# W607B.net
KiCad netlist of a schematic drawn in EAGLE
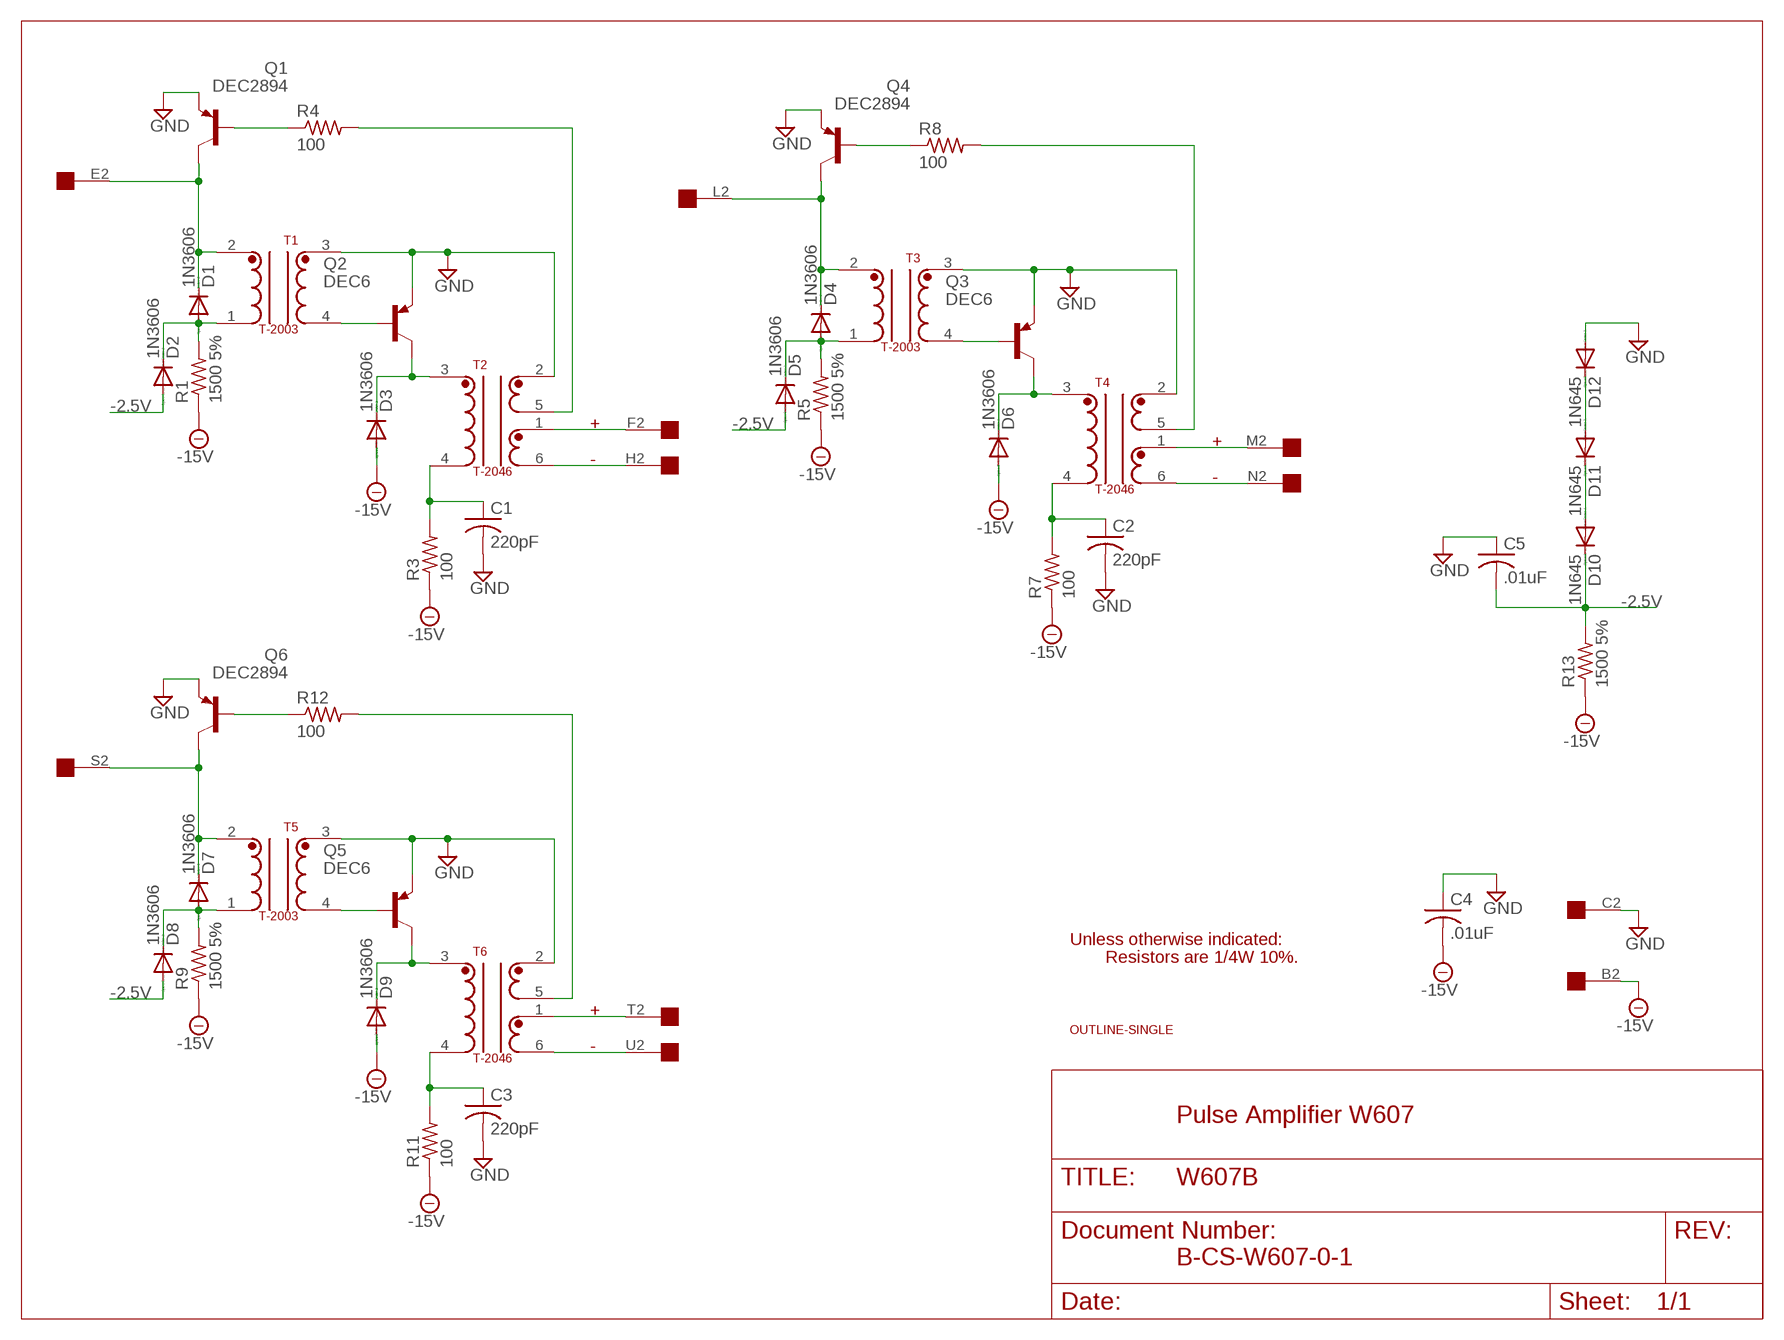
[diagram p0: schematic, sheet 1]

(export (version "E")
  (design (tool "Eeschema 10.0.6"))
  (components
    (comp (ref "C1")
      (value "220pF")
      (footprint "eagle-import:C050-025X075")
      (libsource (lib "eagle-import") (part "C-US050-025X075"))
    )
    (comp (ref "C2")
      (value "220pF")
      (footprint "eagle-import:C050-025X075")
      (libsource (lib "eagle-import") (part "C-US050-025X075"))
    )
    (comp (ref "C3")
      (value "220pF")
      (footprint "eagle-import:C050-025X075")
      (libsource (lib "eagle-import") (part "C-US050-025X075"))
    )
    (comp (ref "C4")
      (value ".01uF")
      (footprint "eagle-import:C050-025X075")
      (libsource (lib "eagle-import") (part "C-US050-025X075"))
    )
    (comp (ref "C5")
      (value ".01uF")
      (footprint "eagle-import:C050-025X075")
      (libsource (lib "eagle-import") (part "C-US050-025X075"))
    )
    (comp (ref "D1")
      (value "1N3606")
      (footprint "eagle-import:DO35-10")
      (libsource (lib "eagle-import") (part "1N4148DO35-10"))
    )
    (comp (ref "D2")
      (value "1N3606")
      (footprint "eagle-import:DO35-10")
      (libsource (lib "eagle-import") (part "1N4148DO35-10"))
    )
    (comp (ref "D3")
      (value "1N3606")
      (footprint "eagle-import:DO35-10")
      (libsource (lib "eagle-import") (part "1N4148DO35-10"))
    )
    (comp (ref "D4")
      (value "1N3606")
      (footprint "eagle-import:DO35-10")
      (libsource (lib "eagle-import") (part "1N4148DO35-10"))
    )
    (comp (ref "D5")
      (value "1N3606")
      (footprint "eagle-import:DO35-10")
      (libsource (lib "eagle-import") (part "1N4148DO35-10"))
    )
    (comp (ref "D6")
      (value "1N3606")
      (footprint "eagle-import:DO35-10")
      (libsource (lib "eagle-import") (part "1N4148DO35-10"))
    )
    (comp (ref "D7")
      (value "1N3606")
      (footprint "eagle-import:DO35-10")
      (libsource (lib "eagle-import") (part "1N4148DO35-10"))
    )
    (comp (ref "D8")
      (value "1N3606")
      (footprint "eagle-import:DO35-10")
      (libsource (lib "eagle-import") (part "1N4148DO35-10"))
    )
    (comp (ref "D9")
      (value "1N3606")
      (footprint "eagle-import:DO35-10")
      (libsource (lib "eagle-import") (part "1N4148DO35-10"))
    )
    (comp (ref "D10")
      (value "1N645")
      (footprint "eagle-import:DO35-10")
      (libsource (lib "eagle-import") (part "1N4148DO35-10"))
    )
    (comp (ref "D11")
      (value "1N645")
      (footprint "eagle-import:DO35-10")
      (libsource (lib "eagle-import") (part "1N4148DO35-10"))
    )
    (comp (ref "D12")
      (value "1N645")
      (footprint "eagle-import:DO35-10")
      (libsource (lib "eagle-import") (part "1N4148DO35-10"))
    )
    (comp (ref "Q1")
      (value "DEC2894")
      (footprint "eagle-import:TO39")
      (libsource (lib "eagle-import") (part "2N2904"))
    )
    (comp (ref "Q2")
      (value "DEC6")
      (footprint "eagle-import:TO39")
      (libsource (lib "eagle-import") (part "2N2904"))
    )
    (comp (ref "Q3")
      (value "DEC6")
      (footprint "eagle-import:TO39")
      (libsource (lib "eagle-import") (part "2N2904"))
    )
    (comp (ref "Q4")
      (value "DEC2894")
      (footprint "eagle-import:TO39")
      (libsource (lib "eagle-import") (part "2N2904"))
    )
    (comp (ref "Q5")
      (value "DEC6")
      (footprint "eagle-import:TO39")
      (libsource (lib "eagle-import") (part "2N2904"))
    )
    (comp (ref "Q6")
      (value "DEC2894")
      (footprint "eagle-import:TO39")
      (libsource (lib "eagle-import") (part "2N2904"))
    )
    (comp (ref "R1")
      (value "1500 5%")
      (footprint "eagle-import:0207_10")
      (libsource (lib "eagle-import") (part "R-US_0207/10"))
    )
    (comp (ref "R3")
      (value "100")
      (footprint "eagle-import:0207_10")
      (libsource (lib "eagle-import") (part "R-US_0207/10"))
    )
    (comp (ref "R4")
      (value "100")
      (footprint "eagle-import:0207_10")
      (libsource (lib "eagle-import") (part "R-US_0207/10"))
    )
    (comp (ref "R5")
      (value "1500 5%")
      (footprint "eagle-import:0207_10")
      (libsource (lib "eagle-import") (part "R-US_0207/10"))
    )
    (comp (ref "R7")
      (value "100")
      (footprint "eagle-import:0207_10")
      (libsource (lib "eagle-import") (part "R-US_0207/10"))
    )
    (comp (ref "R8")
      (value "100")
      (footprint "eagle-import:0207_10")
      (libsource (lib "eagle-import") (part "R-US_0207/10"))
    )
    (comp (ref "R9")
      (value "1500 5%")
      (footprint "eagle-import:0207_10")
      (libsource (lib "eagle-import") (part "R-US_0207/10"))
    )
    (comp (ref "R11")
      (value "100")
      (footprint "eagle-import:0207_10")
      (libsource (lib "eagle-import") (part "R-US_0207/10"))
    )
    (comp (ref "R12")
      (value "100")
      (footprint "eagle-import:0207_10")
      (libsource (lib "eagle-import") (part "R-US_0207/10"))
    )
    (comp (ref "R13")
      (value "1500 5%")
      (footprint "eagle-import:0207_10")
      (libsource (lib "eagle-import") (part "R-US_0207/10"))
    )
    (comp (ref "T1")
      (value "T-2003")
      (footprint "eagle-import:TRANSFORMER2")
      (libsource (lib "eagle-import") (part "T-2010"))
    )
    (comp (ref "T2")
      (value "T-2046")
      (footprint "eagle-import:TRANSFORMER6")
      (libsource (lib "eagle-import") (part "T-2046"))
    )
    (comp (ref "T3")
      (value "T-2003")
      (footprint "eagle-import:TRANSFORMER2")
      (libsource (lib "eagle-import") (part "T-2010"))
    )
    (comp (ref "T4")
      (value "T-2046")
      (footprint "eagle-import:TRANSFORMER6")
      (libsource (lib "eagle-import") (part "T-2046"))
    )
    (comp (ref "T5")
      (value "T-2003")
      (footprint "eagle-import:TRANSFORMER2")
      (libsource (lib "eagle-import") (part "T-2010"))
    )
    (comp (ref "T6")
      (value "T-2046")
      (footprint "eagle-import:TRANSFORMER6")
      (libsource (lib "eagle-import") (part "T-2046"))
    )
    (comp (ref "U$1")
      (value "OUTLINE-SINGLE")
      (footprint "eagle-import:SINGLE")
      (libsource (lib "eagle-import") (part "OUTLINE-SINGLE"))
    )
    (comp (ref "U$2")
      (value "EDGE-1")
      (footprint "eagle-import:EDGE-CON1")
      (libsource (lib "eagle-import") (part "EDGE-1"))
    )
  )
  (nets
    (net (code "1") (name "-15V") (class "Default")
      (node (ref "C4") (pin "2") (pinfunction "2_2") (pintype "passive"))
      (node (ref "D3") (pin "A") (pinfunction "A_A") (pintype "passive"))
      (node (ref "D6") (pin "A") (pinfunction "A_A") (pintype "passive"))
      (node (ref "D9") (pin "A") (pinfunction "A_A") (pintype "passive"))
      (node (ref "R1") (pin "1") (pinfunction "1_1") (pintype "passive"))
      (node (ref "R11") (pin "1") (pinfunction "1_1") (pintype "passive"))
      (node (ref "R13") (pin "1") (pinfunction "1_1") (pintype "passive"))
      (node (ref "R3") (pin "1") (pinfunction "1_1") (pintype "passive"))
      (node (ref "R5") (pin "1") (pinfunction "1_1") (pintype "passive"))
      (node (ref "R7") (pin "1") (pinfunction "1_1") (pintype "passive"))
      (node (ref "R9") (pin "1") (pinfunction "1_1") (pintype "passive"))
      (node (ref "U$2") (pin "B2") (pinfunction "1_B2") (pintype "bidirectional"))
    )
    (net (code "2") (name "/-2.5V") (class "Default")
      (node (ref "C5") (pin "2") (pinfunction "2_2") (pintype "passive"))
      (node (ref "D10") (pin "C") (pinfunction "C_C") (pintype "passive"))
      (node (ref "D2") (pin "A") (pinfunction "A_A") (pintype "passive"))
      (node (ref "D5") (pin "A") (pinfunction "A_A") (pintype "passive"))
      (node (ref "D8") (pin "A") (pinfunction "A_A") (pintype "passive"))
      (node (ref "R13") (pin "2") (pinfunction "2_2") (pintype "passive"))
    )
    (net (code "3") (name "GND") (class "Default")
      (node (ref "C1") (pin "2") (pinfunction "2_2") (pintype "passive"))
      (node (ref "C2") (pin "2") (pinfunction "2_2") (pintype "passive"))
      (node (ref "C3") (pin "2") (pinfunction "2_2") (pintype "passive"))
      (node (ref "C4") (pin "1") (pinfunction "1_1") (pintype "passive"))
      (node (ref "C5") (pin "1") (pinfunction "1_1") (pintype "passive"))
      (node (ref "D12") (pin "A") (pinfunction "A_A") (pintype "passive"))
      (node (ref "Q1") (pin "1") (pinfunction "E_1") (pintype "passive"))
      (node (ref "Q2") (pin "1") (pinfunction "E_1") (pintype "passive"))
      (node (ref "Q3") (pin "1") (pinfunction "E_1") (pintype "passive"))
      (node (ref "Q4") (pin "1") (pinfunction "E_1") (pintype "passive"))
      (node (ref "Q5") (pin "1") (pinfunction "E_1") (pintype "passive"))
      (node (ref "Q6") (pin "1") (pinfunction "E_1") (pintype "passive"))
      (node (ref "T1") (pin "3") (pinfunction "P$2_3") (pintype "passive"))
      (node (ref "T2") (pin "2") (pinfunction "2_2") (pintype "passive"))
      (node (ref "T3") (pin "3") (pinfunction "P$2_3") (pintype "passive"))
      (node (ref "T4") (pin "2") (pinfunction "2_2") (pintype "passive"))
      (node (ref "T5") (pin "3") (pinfunction "P$2_3") (pintype "passive"))
      (node (ref "T6") (pin "2") (pinfunction "2_2") (pintype "passive"))
      (node (ref "U$2") (pin "C2") (pinfunction "1_C2") (pintype "bidirectional"))
    )
    (net (code "4") (name "Net-(C1-Pad1)") (class "Default")
      (node (ref "C1") (pin "1") (pinfunction "1_1") (pintype "passive"))
      (node (ref "R3") (pin "2") (pinfunction "2_2") (pintype "passive"))
      (node (ref "T2") (pin "4") (pinfunction "4_4") (pintype "passive"))
    )
    (net (code "5") (name "Net-(C2-Pad1)") (class "Default")
      (node (ref "C2") (pin "1") (pinfunction "1_1") (pintype "passive"))
      (node (ref "R7") (pin "2") (pinfunction "2_2") (pintype "passive"))
      (node (ref "T4") (pin "4") (pinfunction "4_4") (pintype "passive"))
    )
    (net (code "6") (name "Net-(C3-Pad1)") (class "Default")
      (node (ref "C3") (pin "1") (pinfunction "1_1") (pintype "passive"))
      (node (ref "R11") (pin "2") (pinfunction "2_2") (pintype "passive"))
      (node (ref "T6") (pin "4") (pinfunction "4_4") (pintype "passive"))
    )
    (net (code "7") (name "Net-(D10-PadA)") (class "Default")
      (node (ref "D10") (pin "A") (pinfunction "A_A") (pintype "passive"))
      (node (ref "D11") (pin "C") (pinfunction "C_C") (pintype "passive"))
    )
    (net (code "8") (name "Net-(D11-PadA)") (class "Default")
      (node (ref "D11") (pin "A") (pinfunction "A_A") (pintype "passive"))
      (node (ref "D12") (pin "C") (pinfunction "C_C") (pintype "passive"))
    )
    (net (code "9") (name "Net-(Q1-B)") (class "Default")
      (node (ref "Q1") (pin "2") (pinfunction "B_2") (pintype "passive"))
      (node (ref "R4") (pin "1") (pinfunction "1_1") (pintype "passive"))
    )
    (net (code "10") (name "Net-(Q1-C)") (class "Default")
      (node (ref "D1") (pin "C") (pinfunction "C_C") (pintype "passive"))
      (node (ref "Q1") (pin "3") (pinfunction "C_3") (pintype "passive"))
      (node (ref "T1") (pin "2") (pinfunction "P$4_2") (pintype "passive"))
      (node (ref "U$2") (pin "E2") (pinfunction "1_E2") (pintype "bidirectional"))
    )
    (net (code "11") (name "Net-(Q2-B)") (class "Default")
      (node (ref "Q2") (pin "2") (pinfunction "B_2") (pintype "passive"))
      (node (ref "T1") (pin "4") (pinfunction "P$7_4") (pintype "passive"))
    )
    (net (code "12") (name "Net-(Q2-C)") (class "Default")
      (node (ref "D3") (pin "C") (pinfunction "C_C") (pintype "passive"))
      (node (ref "Q2") (pin "3") (pinfunction "C_3") (pintype "passive"))
      (node (ref "T2") (pin "3") (pinfunction "3_3") (pintype "passive"))
    )
    (net (code "13") (name "Net-(Q3-B)") (class "Default")
      (node (ref "Q3") (pin "2") (pinfunction "B_2") (pintype "passive"))
      (node (ref "T3") (pin "4") (pinfunction "P$7_4") (pintype "passive"))
    )
    (net (code "14") (name "Net-(Q3-C)") (class "Default")
      (node (ref "D6") (pin "C") (pinfunction "C_C") (pintype "passive"))
      (node (ref "Q3") (pin "3") (pinfunction "C_3") (pintype "passive"))
      (node (ref "T4") (pin "3") (pinfunction "3_3") (pintype "passive"))
    )
    (net (code "15") (name "Net-(Q4-B)") (class "Default")
      (node (ref "Q4") (pin "2") (pinfunction "B_2") (pintype "passive"))
      (node (ref "R8") (pin "1") (pinfunction "1_1") (pintype "passive"))
    )
    (net (code "16") (name "Net-(Q4-C)") (class "Default")
      (node (ref "D4") (pin "C") (pinfunction "C_C") (pintype "passive"))
      (node (ref "Q4") (pin "3") (pinfunction "C_3") (pintype "passive"))
      (node (ref "T3") (pin "2") (pinfunction "P$4_2") (pintype "passive"))
      (node (ref "U$2") (pin "L2") (pinfunction "1_L2") (pintype "bidirectional"))
    )
    (net (code "17") (name "Net-(Q5-B)") (class "Default")
      (node (ref "Q5") (pin "2") (pinfunction "B_2") (pintype "passive"))
      (node (ref "T5") (pin "4") (pinfunction "P$7_4") (pintype "passive"))
    )
    (net (code "18") (name "Net-(Q5-C)") (class "Default")
      (node (ref "D9") (pin "C") (pinfunction "C_C") (pintype "passive"))
      (node (ref "Q5") (pin "3") (pinfunction "C_3") (pintype "passive"))
      (node (ref "T6") (pin "3") (pinfunction "3_3") (pintype "passive"))
    )
    (net (code "19") (name "Net-(Q6-B)") (class "Default")
      (node (ref "Q6") (pin "2") (pinfunction "B_2") (pintype "passive"))
      (node (ref "R12") (pin "1") (pinfunction "1_1") (pintype "passive"))
    )
    (net (code "20") (name "Net-(Q6-C)") (class "Default")
      (node (ref "D7") (pin "C") (pinfunction "C_C") (pintype "passive"))
      (node (ref "Q6") (pin "3") (pinfunction "C_3") (pintype "passive"))
      (node (ref "T5") (pin "2") (pinfunction "P$4_2") (pintype "passive"))
      (node (ref "U$2") (pin "S2") (pinfunction "1_S2") (pintype "bidirectional"))
    )
    (net (code "21") (name "Net-(R4-Pad2)") (class "Default")
      (node (ref "R4") (pin "2") (pinfunction "2_2") (pintype "passive"))
      (node (ref "T2") (pin "5") (pinfunction "5_5") (pintype "passive"))
    )
    (net (code "22") (name "Net-(R8-Pad2)") (class "Default")
      (node (ref "R8") (pin "2") (pinfunction "2_2") (pintype "passive"))
      (node (ref "T4") (pin "5") (pinfunction "5_5") (pintype "passive"))
    )
    (net (code "23") (name "Net-(R12-Pad2)") (class "Default")
      (node (ref "R12") (pin "2") (pinfunction "2_2") (pintype "passive"))
      (node (ref "T6") (pin "5") (pinfunction "5_5") (pintype "passive"))
    )
    (net (code "24") (name "Net-(T1-P$5)") (class "Default")
      (node (ref "D1") (pin "A") (pinfunction "A_A") (pintype "passive"))
      (node (ref "D2") (pin "C") (pinfunction "C_C") (pintype "passive"))
      (node (ref "R1") (pin "2") (pinfunction "2_2") (pintype "passive"))
      (node (ref "T1") (pin "1") (pinfunction "P$5_1") (pintype "passive"))
    )
    (net (code "25") (name "Net-(T3-P$5)") (class "Default")
      (node (ref "D4") (pin "A") (pinfunction "A_A") (pintype "passive"))
      (node (ref "D5") (pin "C") (pinfunction "C_C") (pintype "passive"))
      (node (ref "R5") (pin "2") (pinfunction "2_2") (pintype "passive"))
      (node (ref "T3") (pin "1") (pinfunction "P$5_1") (pintype "passive"))
    )
    (net (code "26") (name "Net-(T5-P$5)") (class "Default")
      (node (ref "D7") (pin "A") (pinfunction "A_A") (pintype "passive"))
      (node (ref "D8") (pin "C") (pinfunction "C_C") (pintype "passive"))
      (node (ref "R9") (pin "2") (pinfunction "2_2") (pintype "passive"))
      (node (ref "T5") (pin "1") (pinfunction "P$5_1") (pintype "passive"))
    )
    (net (code "27") (name "Net-(U$2F-1)") (class "Default")
      (node (ref "T2") (pin "1") (pinfunction "1_1") (pintype "passive"))
      (node (ref "U$2") (pin "F2") (pinfunction "1_F2") (pintype "bidirectional"))
    )
    (net (code "28") (name "Net-(U$2G-1)") (class "Default")
      (node (ref "T2") (pin "6") (pinfunction "6_6") (pintype "passive"))
      (node (ref "U$2") (pin "H2") (pinfunction "1_H2") (pintype "bidirectional"))
    )
    (net (code "29") (name "Net-(U$2K-1)") (class "Default")
      (node (ref "T4") (pin "1") (pinfunction "1_1") (pintype "passive"))
      (node (ref "U$2") (pin "M2") (pinfunction "1_M2") (pintype "bidirectional"))
    )
    (net (code "30") (name "Net-(U$2L-1)") (class "Default")
      (node (ref "T4") (pin "6") (pinfunction "6_6") (pintype "passive"))
      (node (ref "U$2") (pin "N2") (pinfunction "1_N2") (pintype "bidirectional"))
    )
    (net (code "31") (name "Net-(U$2P-1)") (class "Default")
      (node (ref "T6") (pin "1") (pinfunction "1_1") (pintype "passive"))
      (node (ref "U$2") (pin "T2") (pinfunction "1_T2") (pintype "bidirectional"))
    )
    (net (code "32") (name "Net-(U$2Q-1)") (class "Default")
      (node (ref "T6") (pin "6") (pinfunction "6_6") (pintype "passive"))
      (node (ref "U$2") (pin "U2") (pinfunction "1_U2") (pintype "bidirectional"))
    )
  )
)
